# Controller_Board.net
KiCad netlist of a schematic drawn in Altium Designer
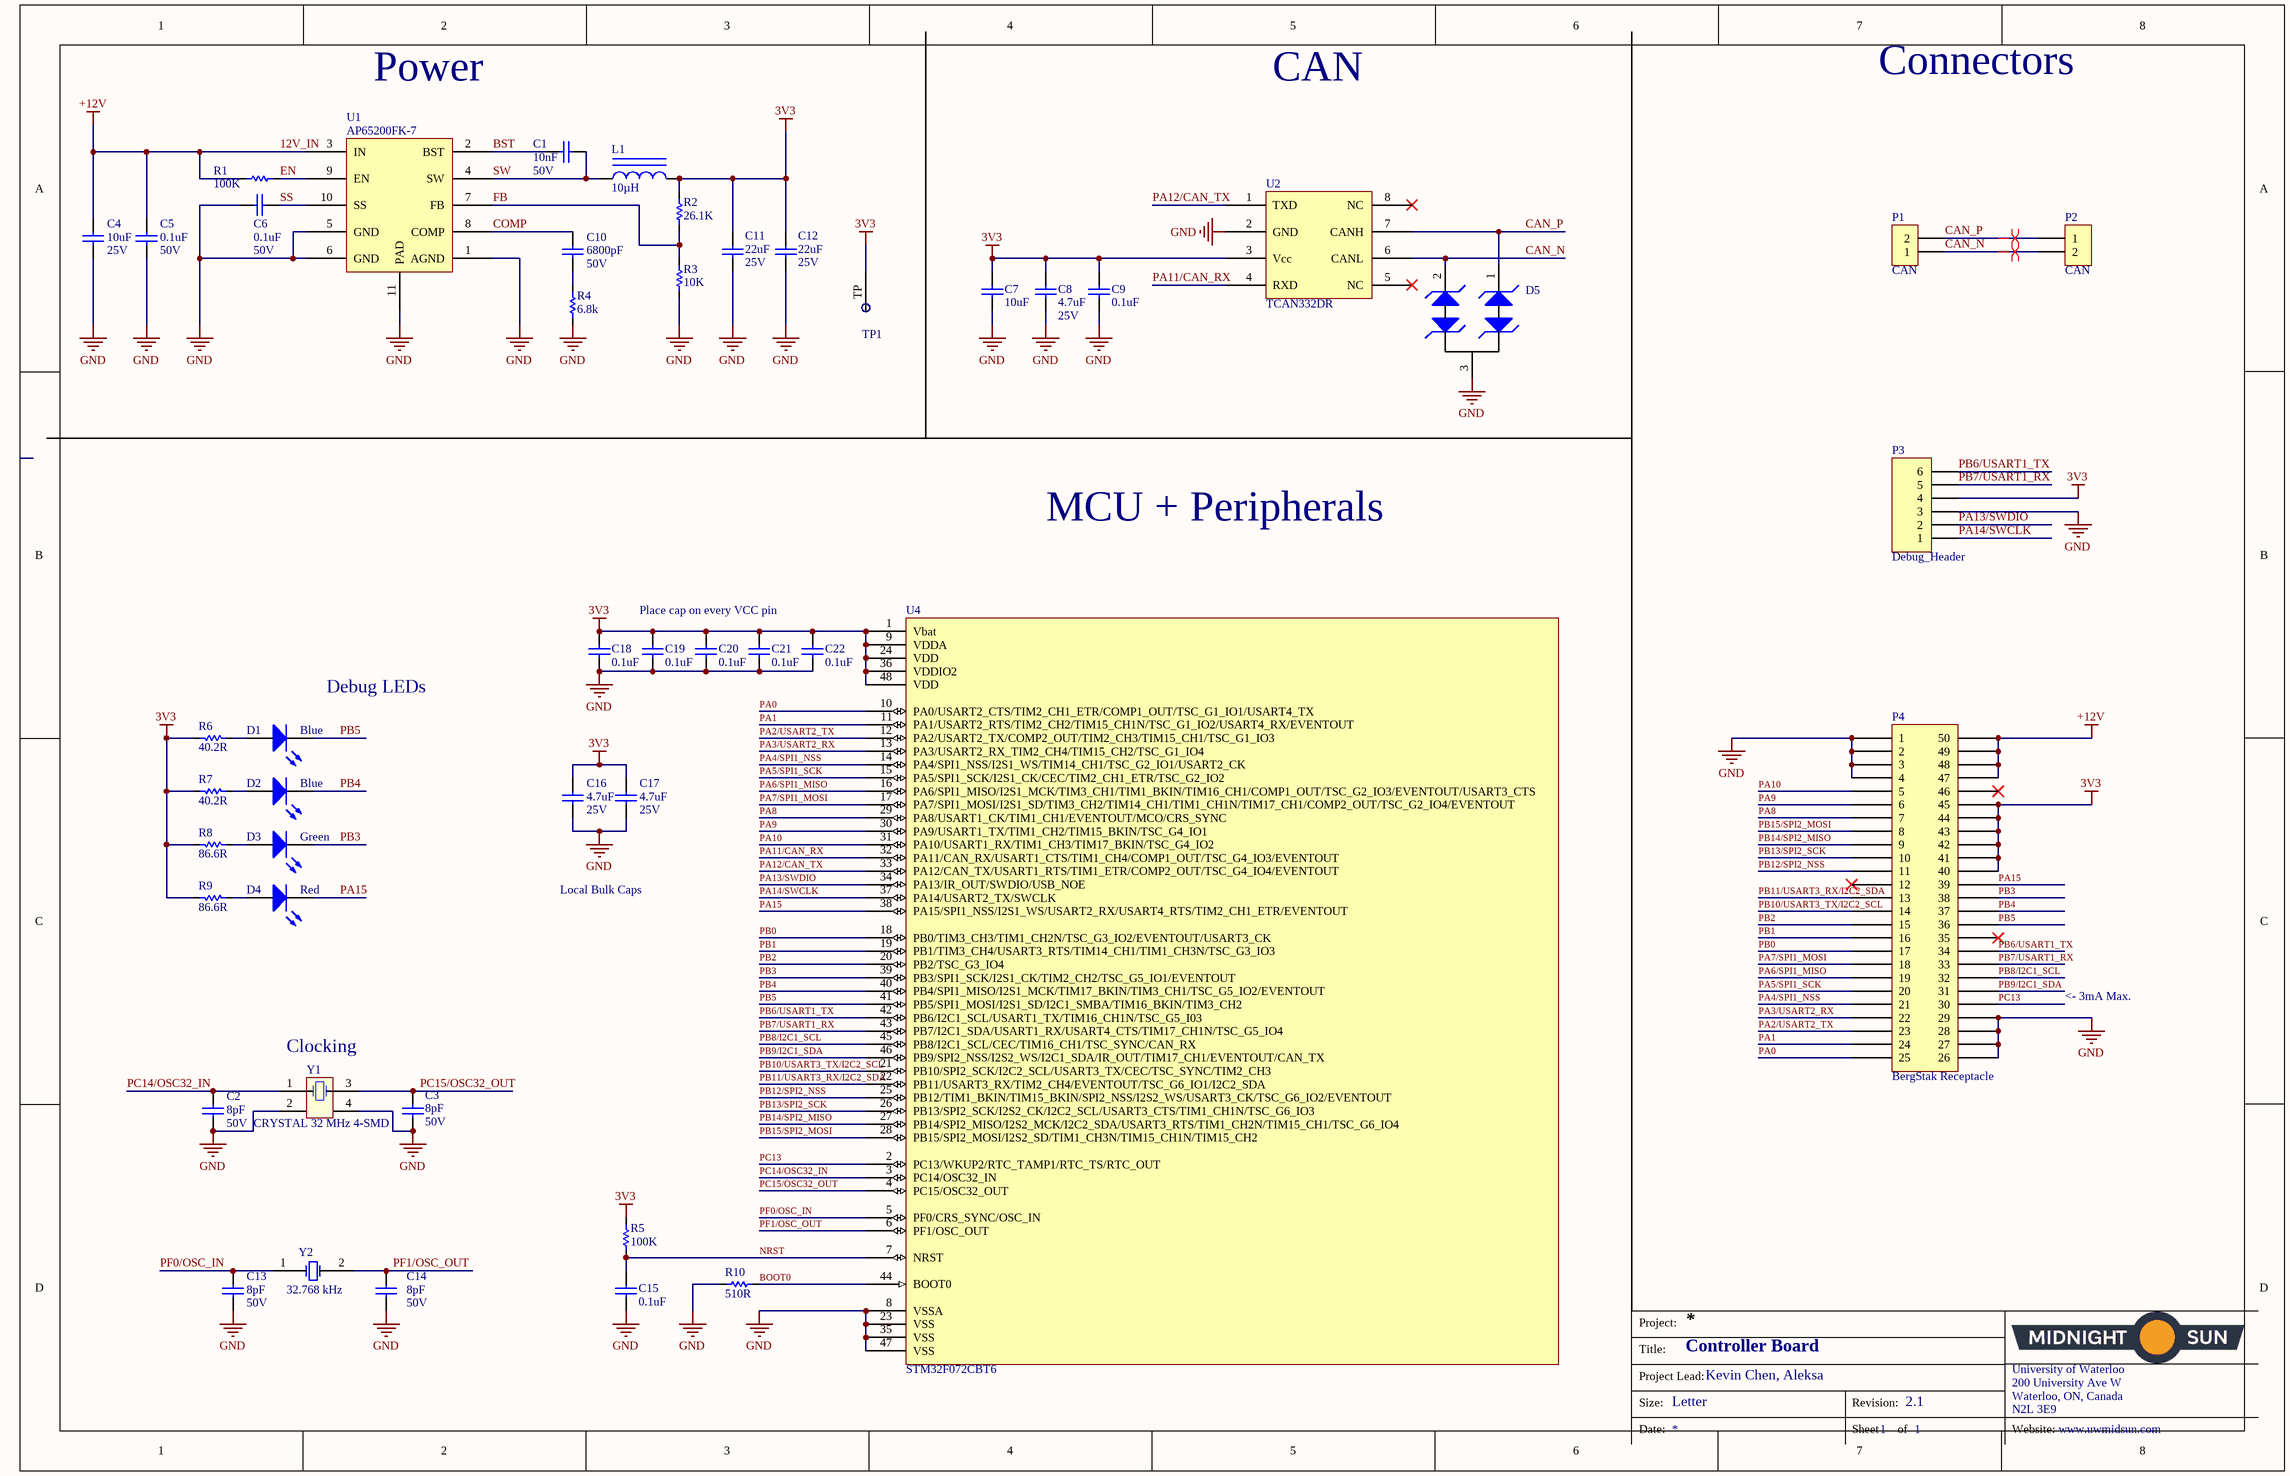
[diagram p0: Controller_Board.SchDoc]

(export (version "E")
  (design (tool "Eeschema 10.0.6"))
  (components
    (comp (ref "C1")
      (value "10nF")
      (footprint "CAPC1608X06N")
      (description "10000pF ±5% 50V Ceramic Capacitor U2J 0603 (1608 Metric)")
      (fields
        (field (name "MANUFACTURER") "Kemet")
        (field (name "MANUFACTURERPARTNUMBER") "C0603C103J5JAC7867")
        (field (name "VOLTAGE") "50V")
      )
      (libsource (lib "Midnight Sun Integrated Library") (part "CAP CER 10nF 50V 5% X7R 0603"))
    )
    (comp (ref "C2")
      (value "8pF")
      (footprint "CAPC1608X06N")
      (description "8pF ±0.5pF 50V Ceramic Capacitor C0G, NP0 0603 (1608 Metric)")
      (fields
        (field (name "MANUFACTURER") "Murata Electronics North America")
        (field (name "MANUFACTURERPARTNUMBER") "GRM1885C1H8R0DA01D")
        (field (name "VOLTAGE") "50V")
      )
      (libsource (lib "Midnight Sun Integrated Library") (part "CAP CER 8PF 50V NP0 0603"))
    )
    (comp (ref "C3")
      (value "8pF")
      (footprint "CAPC1608X06N")
      (description "8pF ±0.5pF 50V Ceramic Capacitor C0G, NP0 0603 (1608 Metric)")
      (fields
        (field (name "MANUFACTURER") "Murata Electronics North America")
        (field (name "MANUFACTURERPARTNUMBER") "GRM1885C1H8R0DA01D")
        (field (name "VOLTAGE") "50V")
      )
      (libsource (lib "Midnight Sun Integrated Library") (part "CAP CER 8PF 50V NP0 0603"))
    )
    (comp (ref "C4")
      (value "10uF")
      (footprint "CAPC1608X06N")
      (description "10µF ±20% 25V Ceramic Capacitor X5R 0603 (1608 Metric)")
      (fields
        (field (name "MANUFACTURER") "Murata Electronics North America")
        (field (name "MANUFACTURERPARTNUMBER") "GRM188R61E106MA73D")
        (field (name "VOLTAGE") "25V")
      )
      (libsource (lib "Midnight Sun Integrated Library") (part "CAP CER 10uF 25V 20% X5R 0603"))
    )
    (comp (ref "C5")
      (value "0.1uF")
      (footprint "CAPC1608X06N")
      (description "0.10µF ±10% 50V Ceramic Capacitor X7R 0603 (1608 Metric)")
      (fields
        (field (name "MANUFACTURER") "AVX Corporation")
        (field (name "MANUFACTURERPARTNUMBER") "06035C104KAT2A")
        (field (name "VOLTAGE") "50V")
      )
      (libsource (lib "Midnight Sun Integrated Library") (part "CAP CER 0.1UF 50V 10% X7R 0603"))
    )
    (comp (ref "C6")
      (value "0.1uF")
      (footprint "CAPC1608X06N")
      (description "0.10µF ±10% 50V Ceramic Capacitor X7R 0603 (1608 Metric)")
      (fields
        (field (name "MANUFACTURER") "AVX Corporation")
        (field (name "MANUFACTURERPARTNUMBER") "06035C104KAT2A")
        (field (name "VOLTAGE") "50V")
      )
      (libsource (lib "Midnight Sun Integrated Library") (part "CAP CER 0.1UF 50V 10% X7R 0603"))
    )
    (comp (ref "C7")
      (value "10uF")
      (footprint "CAPC1608X06N")
      (description "10µF ±20% 25V Ceramic Capacitor X5R 0603 (1608 Metric)")
      (fields
        (field (name "MANUFACTURER") "Murata Electronics North America")
        (field (name "MANUFACTURERPARTNUMBER") "GRM188R61E106MA73D")
      )
      (libsource (lib "Midnight Sun Integrated Library") (part "CAP CER 10uF 25V 20% X5R 0603"))
    )
    (comp (ref "C8")
      (value "4.7uF")
      (footprint "CAPC1608X06N")
      (description "4.7µF ±10% 25V Ceramic Capacitor X5R 0603 (1608 Metric)")
      (fields
        (field (name "MANUFACTURER") "Murata Electronics North America")
        (field (name "MANUFACTURERPARTNUMBER") "GRM188R61E475KE11D")
        (field (name "VOLTAGE") "25V")
      )
      (libsource (lib "Midnight Sun Integrated Library") (part "CAP CER 4.7UF 25V 10% X5R 0603"))
    )
    (comp (ref "C9")
      (value "0.1uF")
      (footprint "CAPC1608X06N")
      (description "0.10µF ±10% 50V Ceramic Capacitor X7R 0603 (1608 Metric)")
      (fields
        (field (name "MANUFACTURER") "AVX Corporation")
        (field (name "MANUFACTURERPARTNUMBER") "06035C104KAT2A")
      )
      (libsource (lib "Midnight Sun Integrated Library") (part "CAP CER 0.1UF 50V 10% X7R 0603"))
    )
    (comp (ref "C10")
      (value "6800pF")
      (footprint "CAPC1608X06N")
      (description "6800pF ±10% 50V Ceramic Capacitor X7R 0603 (1608 Metric)")
      (fields
        (field (name "MANUFACTURER") "Samsung Electro-Mechanics America, Inc.")
        (field (name "MANUFACTURERPARTNUMBER") "CL10B682KB8SFNC")
        (field (name "VOLTAGE") "50V")
      )
      (libsource (lib "Midnight Sun Integrated Library") (part "CAP CER 6800pF 50V 10% X7R 0603"))
    )
    (comp (ref "C11")
      (value "22uF")
      (footprint "CAPC1608X06N")
      (description "0.22µF ±20% 25V Ceramic Capacitor X5R 0603 (1608 Metric)")
      (fields
        (field (name "MANUFACTURER") "Wurth Electronics Inc")
        (field (name "MANUFACTURERPARTNUMBER") "885012106019")
        (field (name "VOLTAGE") "25V")
      )
      (libsource (lib "Midnight Sun Integrated Library") (part "CAP CER 22uF 25V 20% X5R 0603"))
    )
    (comp (ref "C12")
      (value "22uF")
      (footprint "CAPC1608X06N")
      (description "0.22µF ±20% 25V Ceramic Capacitor X5R 0603 (1608 Metric)")
      (fields
        (field (name "MANUFACTURER") "Wurth Electronics Inc")
        (field (name "MANUFACTURERPARTNUMBER") "885012106019")
        (field (name "VOLTAGE") "25V")
      )
      (libsource (lib "Midnight Sun Integrated Library") (part "CAP CER 22uF 25V 20% X5R 0603"))
    )
    (comp (ref "C13")
      (value "8pF")
      (footprint "CAPC1608X06N")
      (description "8pF ±0.5pF 50V Ceramic Capacitor C0G, NP0 0603 (1608 Metric)")
      (fields
        (field (name "MANUFACTURER") "Murata Electronics North America")
        (field (name "MANUFACTURERPARTNUMBER") "GRM1885C1H8R0DA01D")
        (field (name "VOLTAGE") "50V")
      )
      (libsource (lib "Midnight Sun Integrated Library") (part "CAP CER 8PF 50V NP0 0603"))
    )
    (comp (ref "C14")
      (value "8pF")
      (footprint "CAPC1608X06N")
      (description "8pF ±0.5pF 50V Ceramic Capacitor C0G, NP0 0603 (1608 Metric)")
      (fields
        (field (name "MANUFACTURER") "Murata Electronics North America")
        (field (name "MANUFACTURERPARTNUMBER") "GRM1885C1H8R0DA01D")
        (field (name "VOLTAGE") "50V")
      )
      (libsource (lib "Midnight Sun Integrated Library") (part "CAP CER 8PF 50V NP0 0603"))
    )
    (comp (ref "C15")
      (value "0.1uF")
      (footprint "CAPC1608X06N")
      (description "0.10µF ±10% 50V Ceramic Capacitor X7R 0603 (1608 Metric)")
      (fields
        (field (name "MANUFACTURER") "AVX Corporation")
        (field (name "MANUFACTURERPARTNUMBER") "06035C104KAT2A")
      )
      (libsource (lib "Midnight Sun Integrated Library") (part "CAP CER 0.1UF 50V 10% X7R 0603"))
    )
    (comp (ref "C16")
      (value "4.7uF")
      (footprint "CAPC1608X06N")
      (description "4.7µF ±10% 25V Ceramic Capacitor X5R 0603 (1608 Metric)")
      (fields
        (field (name "MANUFACTURER") "Murata Electronics North America")
        (field (name "MANUFACTURERPARTNUMBER") "GRM188R61E475KE11D")
        (field (name "VOLTAGE") "25V")
      )
      (libsource (lib "Midnight Sun Integrated Library") (part "CAP CER 4.7UF 25V 10% X5R 0603"))
    )
    (comp (ref "C17")
      (value "4.7uF")
      (footprint "CAPC1608X06N")
      (description "4.7µF ±10% 25V Ceramic Capacitor X5R 0603 (1608 Metric)")
      (fields
        (field (name "MANUFACTURER") "Murata Electronics North America")
        (field (name "MANUFACTURERPARTNUMBER") "GRM188R61E475KE11D")
        (field (name "VOLTAGE") "25V")
      )
      (libsource (lib "Midnight Sun Integrated Library") (part "CAP CER 4.7UF 25V 10% X5R 0603"))
    )
    (comp (ref "C18")
      (value "0.1uF")
      (footprint "CAPC1608X06N")
      (description "0.10µF ±10% 50V Ceramic Capacitor X7R 0603 (1608 Metric)")
      (fields
        (field (name "MANUFACTURER") "AVX Corporation")
        (field (name "MANUFACTURERPARTNUMBER") "06035C104KAT2A")
      )
      (libsource (lib "Midnight Sun Integrated Library") (part "CAP CER 0.1UF 50V 10% X7R 0603"))
    )
    (comp (ref "C19")
      (value "0.1uF")
      (footprint "CAPC1608X06N")
      (description "0.10µF ±10% 50V Ceramic Capacitor X7R 0603 (1608 Metric)")
      (fields
        (field (name "MANUFACTURER") "AVX Corporation")
        (field (name "MANUFACTURERPARTNUMBER") "06035C104KAT2A")
      )
      (libsource (lib "Midnight Sun Integrated Library") (part "CAP CER 0.1UF 50V 10% X7R 0603"))
    )
    (comp (ref "C20")
      (value "0.1uF")
      (footprint "CAPC1608X06N")
      (description "0.10µF ±10% 50V Ceramic Capacitor X7R 0603 (1608 Metric)")
      (fields
        (field (name "MANUFACTURER") "AVX Corporation")
        (field (name "MANUFACTURERPARTNUMBER") "06035C104KAT2A")
      )
      (libsource (lib "Midnight Sun Integrated Library") (part "CAP CER 0.1UF 50V 10% X7R 0603"))
    )
    (comp (ref "C21")
      (value "0.1uF")
      (footprint "CAPC1608X06N")
      (description "0.10µF ±10% 50V Ceramic Capacitor X7R 0603 (1608 Metric)")
      (fields
        (field (name "MANUFACTURER") "AVX Corporation")
        (field (name "MANUFACTURERPARTNUMBER") "06035C104KAT2A")
      )
      (libsource (lib "Midnight Sun Integrated Library") (part "CAP CER 0.1UF 50V 10% X7R 0603"))
    )
    (comp (ref "C22")
      (value "0.1uF")
      (footprint "CAPC1608X06N")
      (description "0.10µF ±10% 50V Ceramic Capacitor X7R 0603 (1608 Metric)")
      (fields
        (field (name "MANUFACTURER") "AVX Corporation")
        (field (name "MANUFACTURERPARTNUMBER") "06035C104KAT2A")
      )
      (libsource (lib "Midnight Sun Integrated Library") (part "CAP CER 0.1UF 50V 10% X7R 0603"))
    )
    (comp (ref "D1")
      (value "Blue")
      (footprint "DIOC1608X06N")
      (description "LED BLUE CLEAR 0603 SMD")
      (fields
        (field (name "DIGIKEY PART NUMBER") "160-1827-1-ND")
        (field (name "MANUFACTURER") "Lite-On Inc.")
      )
      (libsource (lib "Midnight Sun Integrated Library") (part "LED_BLUE"))
    )
    (comp (ref "D2")
      (value "Blue")
      (footprint "DIOC1608X06N")
      (description "LED BLUE CLEAR 0603 SMD")
      (fields
        (field (name "DIGIKEY PART NUMBER") "160-1827-1-ND")
        (field (name "MANUFACTURER") "Lite-On Inc.")
      )
      (libsource (lib "Midnight Sun Integrated Library") (part "LED_BLUE"))
    )
    (comp (ref "D3")
      (value "Green")
      (footprint "DIOC1608X06N")
      (description "LED GREEN CLEAR 0603 SMD")
      (fields
        (field (name "MANUFACTURER") "Lite-On Inc.")
        (field (name "MANUFACTURER PART NUMBER") "LTST-C193KGKT-5A")
      )
      (libsource (lib "Midnight Sun Integrated Library") (part "LED_GREEN"))
    )
    (comp (ref "D4")
      (value "Red")
      (footprint "DIOC1608X06N")
      (description "Red LED 0603")
      (fields (field (name "MANUFACTURE PART NUMBER") "LTST-C191KRKT"))
      (libsource (lib "Midnight Sun Integrated Library") (part "LED_RED"))
    )
    (comp (ref "D5")
      (value "TVS Diode")
      (footprint "SOT23")
      (description "TVS DIODE 24VWM 70VC SOT23")
      (libsource (lib "Midnight Sun Integrated Library") (part "TVS Diode"))
    )
    (comp (ref "L1")
      (value "10µH")
      (footprint "1210")
      (description "10µH Shielded Wirewound Inductor 900mA 420 mOhm Max 1210 (3225 Metric)")
      (fields
        (field (name "MANUFACTURER") "Murata Electronics North America")
        (field (name "MANUFACTURER PART NUMBER") "1277AS-H-100M=P2")
      )
      (libsource (lib "Midnight Sun Integrated Library") (part "IND 10UH POWDERED IRON 0.9A"))
    )
    (comp (ref "P1")
      (value "CAN")
      (footprint "Dura-Clik, 2POS, 2MM, SMD, Right Angle")
      (description "2 Positions Header, Shrouded Connector 0.079\" (2.00mm) Surface Mount, Right Angle Tin")
      (fields (field (name "MANUFACTURER") "Molex") (field (name "MANUFACTURER PART NUMBER") "5023520200"))
      (libsource (lib "") (part "2 Position DuraClik CAN Connector_1"))
    )
    (comp (ref "P2")
      (value "CAN")
      (footprint "Dura-Clik, 2POS, 2MM, SMD, Right Angle")
      (description "2 Positions Header, Shrouded Connector 0.079\" (2.00mm) Surface Mount, Right Angle Tin")
      (fields (field (name "MANUFACTURER") "Molex") (field (name "MANUFACTURER PART NUMBER") "5023520200"))
      (libsource (lib "Midnight Sun Integrated Library") (part "2 Position DuraClik CAN Connector"))
    )
    (comp (ref "P3")
      (value "Debug_Header")
      (footprint "CONN HEADER 6POS .100\" VERT TIN")
      (description "6 Positions Header, Unshrouded, Breakaway Connector 0.100\" (2.54mm) Surface Mount Tin")
      (fields
        (field (name "MANUFACTURER") "Molex, LLC")
        (field (name "MANUFACTURER PART NUMBER") "0015912060")
      )
      (libsource (lib "Midnight Sun Integrated Library") (part "CONN HEADER 6POS .100 STR TIN"))
    )
    (comp (ref "P4")
      (value "BergStak Receptacle")
      (footprint "609-5227-1-ND")
      (description "50 Position Connector Receptacle, Center Strip Contacts Surface Mount Gold")
      (fields
        (field (name "DIGIKEY PART NUMBER") "609-5227-1-ND")
        (field (name "MANUFACTURER PART NUMBER") "10132798-052100LF")
      )
      (libsource (lib "Midnight Sun Integrated Library") (part "BergStak 50 Position Connector Receptacle"))
    )
    (comp (ref "R1")
      (value "100K")
      (footprint "RESC1608X06N")
      (description "RES SMD 100K OHM 5% 1/10W 0603")
      (fields
        (field (name "MANUFACTURERPARTNUMBER") "RC0603JR-07100KL")
        (field (name "MANUFACTURER") "Yageo")
      )
      (libsource (lib "Midnight Sun Integrated Library") (part "RES 100K OHM 1/8W 5% 0603 SMD"))
    )
    (comp (ref "R2")
      (value "26.1K")
      (footprint "RESC1608X06N")
      (description "RES SMD 26.1K OHM 1% 1/10W 0603")
      (fields
        (field (name "MANUFACTURERPARTNUMBER") "RC0603FR-0726K1L")
        (field (name "MANUFACTURER") "Yageo")
      )
      (libsource (lib "Midnight Sun Integrated Library") (part "RES 26.1K OHM 1/10W 1% 0603 SMD"))
    )
    (comp (ref "R3")
      (value "10K")
      (footprint "RESC1608X06N")
      (description "RES SMD 10K OHM 1% 1/10W 0603")
      (fields (field (name "MANUFACTURE PART NUMBER") "RC0603FR-0710KL") (field (name "TOLERANCE") "1%"))
      (libsource (lib "Midnight Sun Integrated Library") (part "RES SMD 10K OHM 1% 1/10W 0603"))
    )
    (comp (ref "R4")
      (value "6.8k")
      (footprint "RESC1608X06N")
      (description "RES SMD 6.8K OHM 1% 1/10W 0603")
      (fields
        (field (name "MANUFACTURERPARTNUMBER") "RMCF0603FT6K80")
        (field (name "MANUFACTURER") "Stackpole Electronics Inc.")
      )
      (libsource (lib "Midnight Sun Integrated Library") (part "RES 6.8k OHM 1% 1/10W 0603 SMD"))
    )
    (comp (ref "R5")
      (value "100K")
      (footprint "RESC1608X06N")
      (description "RES SMD 100K OHM 5% 1/10W 0603")
      (fields
        (field (name "MANUFACTURERPARTNUMBER") "RC0603JR-07100KL")
        (field (name "MANUFACTURER") "Yageo")
      )
      (libsource (lib "Midnight Sun Integrated Library") (part "RES 100K OHM 1/8W 5% 0603 SMD"))
    )
    (comp (ref "R6")
      (value "40.2R")
      (footprint "RESC1608X06N")
      (description "RES SMD 40.2 OHM 0.5% 1/10W 0603")
      (fields
        (field (name "MANUFACTURERPARTNUMBER") "RT0603DRE0740R2L")
        (field (name "MANUFACTURER") "Yageo")
      )
      (libsource (lib "Midnight Sun Integrated Library") (part "RES 40.2 OHM 0.5% 1/10W 0603 SMD"))
    )
    (comp (ref "R7")
      (value "40.2R")
      (footprint "RESC1608X06N")
      (description "RES SMD 40.2 OHM 0.5% 1/10W 0603")
      (fields
        (field (name "MANUFACTURERPARTNUMBER") "RT0603DRE0740R2L")
        (field (name "MANUFACTURER") "Yageo")
      )
      (libsource (lib "Midnight Sun Integrated Library") (part "RES 40.2 OHM 0.5% 1/10W 0603 SMD"))
    )
    (comp (ref "R8")
      (value "86.6R")
      (footprint "RESC1608X06N")
      (description "RES SMD 86.6 OHM 1% 1/10W 0603")
      (fields
        (field (name "MANUFACTURERPARTNUMBER") "RC0603FR-0786R6L")
        (field (name "MANUFACTURER") "Yageo")
      )
      (libsource (lib "Midnight Sun Integrated Library") (part "RES 86.6 OHM 1% 1/10W 0603 SMD"))
    )
    (comp (ref "R9")
      (value "86.6R")
      (footprint "RESC1608X06N")
      (description "RES SMD 86.6 OHM 1% 1/10W 0603")
      (fields
        (field (name "MANUFACTURERPARTNUMBER") "RC0603FR-0786R6L")
        (field (name "MANUFACTURER") "Yageo")
      )
      (libsource (lib "Midnight Sun Integrated Library") (part "RES 86.6 OHM 1% 1/10W 0603 SMD"))
    )
    (comp (ref "R10")
      (value "510R")
      (footprint "RESC1608X06N")
      (description "RES SMD 510 OHM 5% 1/10W 0603")
      (fields
        (field (name "MANUFACTURERPARTNUMBER") "RC0603JR-07510RL")
        (field (name "MANUFACTURER") "Yageo")
      )
      (libsource (lib "Midnight Sun Integrated Library") (part "RES 510 OHM 1/10W 0603 SMD"))
    )
    (comp (ref "TP1")
      (value "Test Point")
      (footprint "Test Point")
      (libsource (lib "Midnight Sun Integrated Library") (part "Test Point"))
    )
    (comp (ref "U1")
      (value "AP65200FK-7 Buck Switching Regulator")
      (footprint "10-UFDFN")
      (description "Buck Switching Reg IC Positive Adjustable 0.925V 1 Output 2A 10-UFDFN Exposed Pad")
      (fields
        (field (name "DIGIKEY PART NUMBER") "AP65200FK-7DICT-ND")
        (field (name "MANUFACTURER PART NUMBER") "AP65200FK-7")
      )
      (libsource (lib "Midnight Sun Integrated Library") (part "AP65200FK-7 Buck Switching Regulator"))
    )
    (comp (ref "U2")
      (value "TCAN332DR CAN Transceiver")
      (footprint "SOIC8")
      (description "1/1 Transceiver CAN 8-SOIC")
      (fields
        (field (name "DIGIKEY PART NUMBER") "296-43711-1-ND")
        (field (name "MANUFACTURER PART NUMBER") "TCAN332DR")
      )
      (libsource (lib "Midnight Sun Integrated Library") (part "TCAN332DR CAN Transceiver"))
    )
    (comp (ref "U4")
      (value "STM32F072CBT6")
      (footprint "QFN50P700X700X60_HS-49N")
      (fields (field (name "DIGIKEY PART NUMBER") "497-14645-ND"))
      (libsource (lib "Midnight Sun Integrated Library") (part "STM32F072CBT6"))
    )
    (comp (ref "Y1")
      (value "CRYSTAL 32 MHz 4-SMD")
      (footprint "CX2520DB CRYSTAL")
      (description "32MHz ±15ppm Crystal 8pF 50 Ohm -40°C ~ 85°C AEC-Q200 Surface Mount 4-SMD, No Lead")
      (libsource (lib "Midnight Sun Integrated Library") (part "CRYSTAL 32 MHz 4-SMD"))
    )
    (comp (ref "Y2")
      (value "32.768 kHz")
      (footprint "ABS07AIG CRYSTAL")
      (description "32.768kHz ±20ppm Crystal 6pF 50 kOhm -40°C ~ 85°C Surface Mount 4-SOJ, 5.50mm pitch")
      (fields (field (name "MANUFACTURER PART NUMBER") "ABS07AIG-32.768KHZ-9-1-T"))
      (libsource (lib "Midnight Sun Integrated Library") (part "CRYSTAL 32.768KHZ 9PF 2-SMD"))
    )
  )
  (nets
    (net (code "1") (name "+12V") (class "Default")
      (node (ref "C4") (pin "2") (pinfunction "2_2") (pintype "passive"))
      (node (ref "C5") (pin "2") (pinfunction "2_2") (pintype "passive"))
      (node (ref "P4") (pin "47") (pinfunction "47_47") (pintype "passive"))
      (node (ref "P4") (pin "48") (pinfunction "48_48") (pintype "passive"))
      (node (ref "P4") (pin "49") (pinfunction "49_49") (pintype "passive"))
      (node (ref "P4") (pin "50") (pinfunction "50_50") (pintype "passive"))
      (node (ref "R1") (pin "1") (pinfunction "1_1") (pintype "passive"))
      (node (ref "U1") (pin "3") (pinfunction "IN_3") (pintype "passive"))
    )
    (net (code "2") (name "/BOOT0") (class "Default")
      (node (ref "R10") (pin "2") (pinfunction "2_2") (pintype "passive"))
      (node (ref "U4") (pin "44") (pinfunction "BOOT0_44") (pintype "input"))
    )
    (net (code "3") (name "/BST") (class "Default")
      (node (ref "C1") (pin "1") (pinfunction "1_1") (pintype "passive"))
      (node (ref "U1") (pin "2") (pinfunction "BST_2") (pintype "passive"))
    )
    (net (code "4") (name "/CAN_N") (class "Default")
      (node (ref "D5") (pin "2") (pinfunction "Cathode2_2") (pintype "passive"))
      (node (ref "P1") (pin "1") (pinfunction "1_1") (pintype "passive"))
      (node (ref "P2") (pin "2") (pinfunction "2_2") (pintype "passive"))
      (node (ref "U2") (pin "6") (pinfunction "CANL_6") (pintype "passive"))
    )
    (net (code "5") (name "/CAN_P") (class "Default")
      (node (ref "D5") (pin "1") (pinfunction "Cathode1_1") (pintype "passive"))
      (node (ref "P1") (pin "2") (pinfunction "2_2") (pintype "passive"))
      (node (ref "P2") (pin "1") (pinfunction "1_1") (pintype "passive"))
      (node (ref "U2") (pin "7") (pinfunction "CANH_7") (pintype "passive"))
    )
    (net (code "6") (name "/COMP") (class "Default")
      (node (ref "C10") (pin "2") (pinfunction "2_2") (pintype "passive"))
      (node (ref "U1") (pin "8") (pinfunction "COMP_8") (pintype "passive"))
    )
    (net (code "7") (name "/EN") (class "Default")
      (node (ref "R1") (pin "2") (pinfunction "2_2") (pintype "passive"))
      (node (ref "U1") (pin "9") (pinfunction "EN_9") (pintype "passive"))
    )
    (net (code "8") (name "/FB") (class "Default")
      (node (ref "R2") (pin "1") (pinfunction "1_1") (pintype "passive"))
      (node (ref "R3") (pin "2") (pinfunction "2_2") (pintype "passive"))
      (node (ref "U1") (pin "7") (pinfunction "FB_7") (pintype "passive"))
    )
    (net (code "9") (name "/NRST") (class "Default")
      (node (ref "C15") (pin "2") (pinfunction "2_2") (pintype "passive"))
      (node (ref "R5") (pin "1") (pinfunction "1_1") (pintype "passive"))
      (node (ref "U4") (pin "7") (pinfunction "NRST_7") (pintype "bidirectional"))
    )
    (net (code "10") (name "/PA0") (class "Default")
      (node (ref "P4") (pin "25") (pinfunction "25_25") (pintype "passive"))
      (node (ref "U4") (pin "10") (pinfunction "PA0/USART2_CTS/TIM2_CH1_ETR/COMP1_OUT/TSC_G1_IO1/USART4_TX_10") (pintype "bidirectional"))
    )
    (net (code "11") (name "/PA1") (class "Default")
      (node (ref "P4") (pin "24") (pinfunction "24_24") (pintype "passive"))
      (node (ref "U4") (pin "11") (pinfunction "PA1/USART2_RTS/TIM2_CH2/TIM15_CH1N/TSC_G1_IO2/USART4_RX/EVENTOUT_11") (pintype "bidirectional"))
    )
    (net (code "12") (name "/PA2{slash}USART2_TX") (class "Default")
      (node (ref "P4") (pin "23") (pinfunction "23_23") (pintype "passive"))
      (node (ref "U4") (pin "12") (pinfunction "PA2/USART2_TX/COMP2_OUT/TIM2_CH3/TIM15_CH1/TSC_G1_IO3_12") (pintype "bidirectional"))
    )
    (net (code "13") (name "/PA3{slash}USART2_RX") (class "Default")
      (node (ref "P4") (pin "22") (pinfunction "22_22") (pintype "passive"))
      (node (ref "U4") (pin "13") (pinfunction "PA3/USART2_RX_TIM2_CH4/TIM15_CH2/TSC_G1_IO4_13") (pintype "bidirectional"))
    )
    (net (code "14") (name "/PA4{slash}SPI1_NSS") (class "Default")
      (node (ref "P4") (pin "21") (pinfunction "21_21") (pintype "passive"))
      (node (ref "U4") (pin "14") (pinfunction "PA4/SPI1_NSS/I2S1_WS/TIM14_CH1/TSC_G2_IO1/USART2_CK_14") (pintype "bidirectional"))
    )
    (net (code "15") (name "/PA5{slash}SPI1_SCK") (class "Default")
      (node (ref "P4") (pin "20") (pinfunction "20_20") (pintype "passive"))
      (node (ref "U4") (pin "15") (pinfunction "PA5/SPI1_SCK/I2S1_CK/CEC/TIM2_CH1_ETR/TSC_G2_IO2_15") (pintype "bidirectional"))
    )
    (net (code "16") (name "/PA6{slash}SPI1_MISO") (class "Default")
      (node (ref "P4") (pin "19") (pinfunction "19_19") (pintype "passive"))
      (node (ref "U4") (pin "16") (pinfunction "PA6/SPI1_MISO/I2S1_MCK/TIM3_CH1/TIM1_BKIN/TIM16_CH1/COMP1_OUT/TSC_G2_IO3/EVENTOUT/USART3_CTS_16") (pintype "bidirectional"))
    )
    (net (code "17") (name "/PA7{slash}SPI1_MOSI") (class "Default")
      (node (ref "P4") (pin "18") (pinfunction "18_18") (pintype "passive"))
      (node (ref "U4") (pin "17") (pinfunction "PA7/SPI1_MOSI/I2S1_SD/TIM3_CH2/TIM14_CH1/TIM1_CH1N/TIM17_CH1/COMP2_OUT/TSC_G2_IO4/EVENTOUT_17") (pintype "bidirectional"))
    )
    (net (code "18") (name "/PA8") (class "Default")
      (node (ref "P4") (pin "7") (pinfunction "7_7") (pintype "passive"))
      (node (ref "U4") (pin "29") (pinfunction "PA8/USART1_CK/TIM1_CH1/EVENTOUT/MCO/CRS_SYNC_29") (pintype "bidirectional"))
    )
    (net (code "19") (name "/PA9") (class "Default")
      (node (ref "P4") (pin "6") (pinfunction "6_6") (pintype "passive"))
      (node (ref "U4") (pin "30") (pinfunction "PA9/USART1_TX/TIM1_CH2/TIM15_BKIN/TSC_G4_IO1_30") (pintype "bidirectional"))
    )
    (net (code "20") (name "/PA10") (class "Default")
      (node (ref "P4") (pin "5") (pinfunction "5_5") (pintype "passive"))
      (node (ref "U4") (pin "31") (pinfunction "PA10/USART1_RX/TIM1_CH3/TIM17_BKIN/TSC_G4_IO2_31") (pintype "bidirectional"))
    )
    (net (code "21") (name "/PA11{slash}CAN_RX") (class "Default")
      (node (ref "U2") (pin "4") (pinfunction "RXD_4") (pintype "passive"))
      (node (ref "U4") (pin "32") (pinfunction "PA11/CAN_RX/USART1_CTS/TIM1_CH4/COMP1_OUT/TSC_G4_IO3/EVENTOUT_32") (pintype "bidirectional"))
    )
    (net (code "22") (name "/PA12{slash}CAN_TX") (class "Default")
      (node (ref "U2") (pin "1") (pinfunction "TXD_1") (pintype "passive"))
      (node (ref "U4") (pin "33") (pinfunction "PA12/CAN_TX/USART1_RTS/TIM1_ETR/COMP2_OUT/TSC_G4_IO4/EVENTOUT_33") (pintype "bidirectional"))
    )
    (net (code "23") (name "/PA13{slash}SWDIO") (class "Default")
      (node (ref "P3") (pin "2") (pinfunction "2_2") (pintype "passive"))
      (node (ref "U4") (pin "34") (pinfunction "PA13/IR_OUT/SWDIO/USB_NOE_34") (pintype "bidirectional"))
    )
    (net (code "24") (name "/PA14{slash}SWCLK") (class "Default")
      (node (ref "P3") (pin "1") (pinfunction "1_1") (pintype "passive"))
      (node (ref "U4") (pin "37") (pinfunction "PA14/USART2_TX/SWCLK_37") (pintype "bidirectional"))
    )
    (net (code "25") (name "/PA15") (class "Default")
      (node (ref "D4") (pin "2") (pinfunction "K_2") (pintype "passive"))
      (node (ref "P4") (pin "39") (pinfunction "39_39") (pintype "passive"))
      (node (ref "U4") (pin "38") (pinfunction "PA15/SPI1_NSS/I2S1_WS/USART2_RX/USART4_RTS/TIM2_CH1_ETR/EVENTOUT_38") (pintype "bidirectional"))
    )
    (net (code "26") (name "/PB0") (class "Default")
      (node (ref "P4") (pin "17") (pinfunction "17_17") (pintype "passive"))
      (node (ref "U4") (pin "18") (pinfunction "PB0/TIM3_CH3/TIM1_CH2N/TSC_G3_IO2/EVENTOUT/USART3_CK_18") (pintype "bidirectional"))
    )
    (net (code "27") (name "/PB1") (class "Default")
      (node (ref "P4") (pin "16") (pinfunction "16_16") (pintype "passive"))
      (node (ref "U4") (pin "19") (pinfunction "PB1/TIM3_CH4/USART3_RTS/TIM14_CH1/TIM1_CH3N/TSC_G3_IO3_19") (pintype "bidirectional"))
    )
    (net (code "28") (name "/PB2") (class "Default")
      (node (ref "P4") (pin "15") (pinfunction "15_15") (pintype "passive"))
      (node (ref "U4") (pin "20") (pinfunction "PB2/TSC_G3_IO4_20") (pintype "bidirectional"))
    )
    (net (code "29") (name "/PB3") (class "Default")
      (node (ref "D3") (pin "2") (pinfunction "K_2") (pintype "passive"))
      (node (ref "P4") (pin "38") (pinfunction "38_38") (pintype "passive"))
      (node (ref "U4") (pin "39") (pinfunction "PB3/SPI1_SCK/I2S1_CK/TIM2_CH2/TSC_G5_IO1/EVENTOUT_39") (pintype "bidirectional"))
    )
    (net (code "30") (name "/PB4") (class "Default")
      (node (ref "D2") (pin "2") (pinfunction "K_2") (pintype "passive"))
      (node (ref "P4") (pin "37") (pinfunction "37_37") (pintype "passive"))
      (node (ref "U4") (pin "40") (pinfunction "PB4/SPI1_MISO/I2S1_MCK/TIM17_BKIN/TIM3_CH1/TSC_G5_IO2/EVENTOUT_40") (pintype "bidirectional"))
    )
    (net (code "31") (name "/PB5") (class "Default")
      (node (ref "D1") (pin "2") (pinfunction "K_2") (pintype "passive"))
      (node (ref "P4") (pin "36") (pinfunction "36_36") (pintype "passive"))
      (node (ref "U4") (pin "41") (pinfunction "PB5/SPI1_MOSI/I2S1_SD/I2C1_SMBA/TIM16_BKIN/TIM3_CH2_41") (pintype "bidirectional"))
    )
    (net (code "32") (name "/PB6{slash}USART1_TX") (class "Default")
      (node (ref "P3") (pin "6") (pinfunction "6_6") (pintype "passive"))
      (node (ref "P4") (pin "34") (pinfunction "34_34") (pintype "passive"))
      (node (ref "U4") (pin "42") (pinfunction "PB6/I2C1_SCL/USART1_TX/TIM16_CH1N/TSC_G5_I03_42") (pintype "bidirectional"))
    )
    (net (code "33") (name "/PB7{slash}USART1_RX") (class "Default")
      (node (ref "P3") (pin "5") (pinfunction "5_5") (pintype "passive"))
      (node (ref "P4") (pin "33") (pinfunction "33_33") (pintype "passive"))
      (node (ref "U4") (pin "43") (pinfunction "PB7/I2C1_SDA/USART1_RX/USART4_CTS/TIM17_CH1N/TSC_G5_IO4_43") (pintype "bidirectional"))
    )
    (net (code "34") (name "/PB8{slash}I2C1_SCL") (class "Default")
      (node (ref "P4") (pin "32") (pinfunction "32_32") (pintype "passive"))
      (node (ref "U4") (pin "45") (pinfunction "PB8/I2C1_SCL/CEC/TIM16_CH1/TSC_SYNC/CAN_RX_45") (pintype "bidirectional"))
    )
    (net (code "35") (name "/PB9{slash}I2C1_SDA") (class "Default")
      (node (ref "P4") (pin "31") (pinfunction "31_31") (pintype "passive"))
      (node (ref "U4") (pin "46") (pinfunction "PB9/SPI2_NSS/I2S2_WS/I2C1_SDA/IR_OUT/TIM17_CH1/EVENTOUT/CAN_TX_46") (pintype "bidirectional"))
    )
    (net (code "36") (name "/PB10{slash}USART3_TX{slash}I2C2_SCL") (class "Default")
      (node (ref "P4") (pin "14") (pinfunction "14_14") (pintype "passive"))
      (node (ref "U4") (pin "21") (pinfunction "PB10/SPI2_SCK/I2C2_SCL/USART3_TX/CEC/TSC_SYNC/TIM2_CH3_21") (pintype "bidirectional"))
    )
    (net (code "37") (name "/PB11{slash}USART3_RX{slash}I2C2_SDA") (class "Default")
      (node (ref "P4") (pin "13") (pinfunction "13_13") (pintype "passive"))
      (node (ref "U4") (pin "22") (pinfunction "PB11/USART3_RX/TIM2_CH4/EVENTOUT/TSC_G6_IO1/I2C2_SDA_22") (pintype "bidirectional"))
    )
    (net (code "38") (name "/PB12{slash}SPI2_NSS") (class "Default")
      (node (ref "P4") (pin "11") (pinfunction "11_11") (pintype "passive"))
      (node (ref "U4") (pin "25") (pinfunction "PB12/TIM1_BKIN/TIM15_BKIN/SPI2_NSS/I2S2_WS/USART3_CK/TSC_G6_IO2/EVENTOUT_25") (pintype "bidirectional"))
    )
    (net (code "39") (name "/PB13{slash}SPI2_SCK") (class "Default")
      (node (ref "P4") (pin "10") (pinfunction "10_10") (pintype "passive"))
      (node (ref "U4") (pin "26") (pinfunction "PB13/SPI2_SCK/I2S2_CK/I2C2_SCL/USART3_CTS/TIM1_CH1N/TSC_G6_IO3_26") (pintype "bidirectional"))
    )
    (net (code "40") (name "/PB14{slash}SPI2_MISO") (class "Default")
      (node (ref "P4") (pin "9") (pinfunction "9_9") (pintype "passive"))
      (node (ref "U4") (pin "27") (pinfunction "PB14/SPI2_MISO/I2S2_MCK/I2C2_SDA/USART3_RTS/TIM1_CH2N/TIM15_CH1/TSC_G6_IO4_27") (pintype "bidirectional"))
    )
    (net (code "41") (name "/PB15{slash}SPI2_MOSI") (class "Default")
      (node (ref "P4") (pin "8") (pinfunction "8_8") (pintype "passive"))
      (node (ref "U4") (pin "28") (pinfunction "PB15/SPI2_MOSI/I2S2_SD/TIM1_CH3N/TIM15_CH1N/TIM15_CH2_28") (pintype "bidirectional"))
    )
    (net (code "42") (name "/PC13") (class "Default")
      (node (ref "P4") (pin "30") (pinfunction "30_30") (pintype "passive"))
      (node (ref "U4") (pin "2") (pinfunction "PC13/WKUP2/RTC_TAMP1/RTC_TS/RTC_OUT_2") (pintype "bidirectional"))
    )
    (net (code "43") (name "/PC14{slash}OSC32_IN") (class "Default")
      (node (ref "C2") (pin "2") (pinfunction "2_2") (pintype "passive"))
      (node (ref "U4") (pin "3") (pinfunction "PC14/OSC32_IN_3") (pintype "bidirectional"))
      (node (ref "Y1") (pin "1") (pinfunction "OSC1_1") (pintype "passive"))
    )
    (net (code "44") (name "/PC15{slash}OSC32_OUT") (class "Default")
      (node (ref "C3") (pin "2") (pinfunction "2_2") (pintype "passive"))
      (node (ref "U4") (pin "4") (pinfunction "PC15/OSC32_OUT_4") (pintype "bidirectional"))
      (node (ref "Y1") (pin "3") (pinfunction "OSC2_3") (pintype "passive"))
    )
    (net (code "45") (name "/PF0{slash}OSC_IN") (class "Default")
      (node (ref "C13") (pin "2") (pinfunction "2_2") (pintype "passive"))
      (node (ref "U4") (pin "5") (pinfunction "PF0/CRS_SYNC/OSC_IN_5") (pintype "bidirectional"))
      (node (ref "Y2") (pin "1") (pinfunction "1_1") (pintype "passive"))
    )
    (net (code "46") (name "/PF1{slash}OSC_OUT") (class "Default")
      (node (ref "C14") (pin "2") (pinfunction "2_2") (pintype "passive"))
      (node (ref "U4") (pin "6") (pinfunction "PF1/OSC_OUT_6") (pintype "bidirectional"))
      (node (ref "Y2") (pin "2") (pinfunction "2_2") (pintype "passive"))
    )
    (net (code "47") (name "/SS") (class "Default")
      (node (ref "C6") (pin "1") (pinfunction "1_1") (pintype "passive"))
      (node (ref "U1") (pin "10") (pinfunction "SS_10") (pintype "passive"))
    )
    (net (code "48") (name "/SW") (class "Default")
      (node (ref "C1") (pin "2") (pinfunction "2_2") (pintype "passive"))
      (node (ref "L1") (pin "1") (pinfunction "1_1") (pintype "passive"))
      (node (ref "U1") (pin "4") (pinfunction "SW_4") (pintype "passive"))
    )
    (net (code "49") (name "3V3") (class "Default")
      (node (ref "C11") (pin "2") (pinfunction "2_2") (pintype "passive"))
      (node (ref "C12") (pin "2") (pinfunction "2_2") (pintype "passive"))
      (node (ref "C16") (pin "2") (pinfunction "2_2") (pintype "passive"))
      (node (ref "C17") (pin "2") (pinfunction "2_2") (pintype "passive"))
      (node (ref "C18") (pin "2") (pinfunction "2_2") (pintype "passive"))
      (node (ref "C19") (pin "2") (pinfunction "2_2") (pintype "passive"))
      (node (ref "C20") (pin "2") (pinfunction "2_2") (pintype "passive"))
      (node (ref "C21") (pin "2") (pinfunction "2_2") (pintype "passive"))
      (node (ref "C22") (pin "2") (pinfunction "2_2") (pintype "passive"))
      (node (ref "C7") (pin "2") (pinfunction "2_2") (pintype "passive"))
      (node (ref "C8") (pin "2") (pinfunction "2_2") (pintype "passive"))
      (node (ref "C9") (pin "2") (pinfunction "2_2") (pintype "passive"))
      (node (ref "L1") (pin "2") (pinfunction "2_2") (pintype "passive"))
      (node (ref "P3") (pin "4") (pinfunction "4_4") (pintype "passive"))
      (node (ref "P4") (pin "40") (pinfunction "40_40") (pintype "passive"))
      (node (ref "P4") (pin "41") (pinfunction "41_41") (pintype "passive"))
      (node (ref "P4") (pin "42") (pinfunction "42_42") (pintype "passive"))
      (node (ref "P4") (pin "43") (pinfunction "43_43") (pintype "passive"))
      (node (ref "P4") (pin "44") (pinfunction "44_44") (pintype "passive"))
      (node (ref "P4") (pin "45") (pinfunction "45_45") (pintype "passive"))
      (node (ref "R2") (pin "2") (pinfunction "2_2") (pintype "passive"))
      (node (ref "R5") (pin "2") (pinfunction "2_2") (pintype "passive"))
      (node (ref "R6") (pin "2") (pinfunction "2_2") (pintype "passive"))
      (node (ref "R7") (pin "2") (pinfunction "2_2") (pintype "passive"))
      (node (ref "R8") (pin "2") (pinfunction "2_2") (pintype "passive"))
      (node (ref "R9") (pin "2") (pinfunction "2_2") (pintype "passive"))
      (node (ref "TP1") (pin "TP") (pinfunction "1_TP") (pintype "passive"))
      (node (ref "U2") (pin "3") (pinfunction "Vcc_3") (pintype "passive"))
      (node (ref "U4") (pin "1") (pinfunction "Vbat_1") (pintype "power_in"))
      (node (ref "U4") (pin "24") (pinfunction "VDD_24") (pintype "power_in"))
      (node (ref "U4") (pin "36") (pinfunction "VDDIO2_36") (pintype "power_in"))
      (node (ref "U4") (pin "48") (pinfunction "VDD_48") (pintype "power_in"))
      (node (ref "U4") (pin "9") (pinfunction "VDDA_9") (pintype "power_in"))
    )
    (net (code "50") (name "GND") (class "Default")
      (node (ref "C11") (pin "1") (pinfunction "1_1") (pintype "passive"))
      (node (ref "C12") (pin "1") (pinfunction "1_1") (pintype "passive"))
      (node (ref "C13") (pin "1") (pinfunction "1_1") (pintype "passive"))
      (node (ref "C14") (pin "1") (pinfunction "1_1") (pintype "passive"))
      (node (ref "C15") (pin "1") (pinfunction "1_1") (pintype "passive"))
      (node (ref "C16") (pin "1") (pinfunction "1_1") (pintype "passive"))
      (node (ref "C17") (pin "1") (pinfunction "1_1") (pintype "passive"))
      (node (ref "C18") (pin "1") (pinfunction "1_1") (pintype "passive"))
      (node (ref "C19") (pin "1") (pinfunction "1_1") (pintype "passive"))
      (node (ref "C2") (pin "1") (pinfunction "1_1") (pintype "passive"))
      (node (ref "C20") (pin "1") (pinfunction "1_1") (pintype "passive"))
      (node (ref "C21") (pin "1") (pinfunction "1_1") (pintype "passive"))
      (node (ref "C22") (pin "1") (pinfunction "1_1") (pintype "passive"))
      (node (ref "C3") (pin "1") (pinfunction "1_1") (pintype "passive"))
      (node (ref "C4") (pin "1") (pinfunction "1_1") (pintype "passive"))
      (node (ref "C5") (pin "1") (pinfunction "1_1") (pintype "passive"))
      (node (ref "C6") (pin "2") (pinfunction "2_2") (pintype "passive"))
      (node (ref "C7") (pin "1") (pinfunction "1_1") (pintype "passive"))
      (node (ref "C8") (pin "1") (pinfunction "1_1") (pintype "passive"))
      (node (ref "C9") (pin "1") (pinfunction "1_1") (pintype "passive"))
      (node (ref "D5") (pin "3") (pinfunction "Common_Cathode_3") (pintype "power_in"))
      (node (ref "P3") (pin "3") (pinfunction "3_3") (pintype "passive"))
      (node (ref "P4") (pin "1") (pinfunction "1_1") (pintype "passive"))
      (node (ref "P4") (pin "2") (pinfunction "2_2") (pintype "passive"))
      (node (ref "P4") (pin "26") (pinfunction "26_26") (pintype "passive"))
      (node (ref "P4") (pin "27") (pinfunction "27_27") (pintype "passive"))
      (node (ref "P4") (pin "28") (pinfunction "28_28") (pintype "passive"))
      (node (ref "P4") (pin "29") (pinfunction "29_29") (pintype "passive"))
      (node (ref "P4") (pin "3") (pinfunction "3_3") (pintype "passive"))
      (node (ref "P4") (pin "4") (pinfunction "4_4") (pintype "passive"))
      (node (ref "R10") (pin "1") (pinfunction "1_1") (pintype "passive"))
      (node (ref "R3") (pin "1") (pinfunction "1_1") (pintype "passive"))
      (node (ref "R4") (pin "1") (pinfunction "1_1") (pintype "passive"))
      (node (ref "U1") (pin "1") (pinfunction "AGND_1") (pintype "passive"))
      (node (ref "U1") (pin "11") (pinfunction "PAD_11") (pintype "passive"))
      (node (ref "U1") (pin "5") (pinfunction "GND_5") (pintype "power_in"))
      (node (ref "U1") (pin "6") (pinfunction "GND_6") (pintype "power_in"))
      (node (ref "U2") (pin "2") (pinfunction "GND_2") (pintype "passive"))
      (node (ref "U4") (pin "23") (pinfunction "VSS_23") (pintype "power_in"))
      (node (ref "U4") (pin "35") (pinfunction "VSS_35") (pintype "power_in"))
      (node (ref "U4") (pin "47") (pinfunction "VSS_47") (pintype "power_in"))
      (node (ref "U4") (pin "8") (pinfunction "VSSA_8") (pintype "power_in"))
      (node (ref "Y1") (pin "2") (pinfunction "2_2") (pintype "passive"))
      (node (ref "Y1") (pin "4") (pinfunction "3_4") (pintype "passive"))
    )
    (net (code "51") (name "Net-(C10-Pad1)") (class "Default")
      (node (ref "C10") (pin "1") (pinfunction "1_1") (pintype "passive"))
      (node (ref "R4") (pin "2") (pinfunction "2_2") (pintype "passive"))
    )
    (net (code "52") (name "Net-(D1-A)") (class "Default")
      (node (ref "D1") (pin "1") (pinfunction "A_1") (pintype "passive"))
      (node (ref "R6") (pin "1") (pinfunction "1_1") (pintype "passive"))
    )
    (net (code "53") (name "Net-(D2-A)") (class "Default")
      (node (ref "D2") (pin "1") (pinfunction "A_1") (pintype "passive"))
      (node (ref "R7") (pin "1") (pinfunction "1_1") (pintype "passive"))
    )
    (net (code "54") (name "Net-(D3-A)") (class "Default")
      (node (ref "D3") (pin "1") (pinfunction "A_1") (pintype "passive"))
      (node (ref "R8") (pin "1") (pinfunction "1_1") (pintype "passive"))
    )
    (net (code "55") (name "Net-(D4-A)") (class "Default")
      (node (ref "D4") (pin "1") (pinfunction "A_1") (pintype "passive"))
      (node (ref "R9") (pin "1") (pinfunction "1_1") (pintype "passive"))
    )
    (net (code "56") (name "unconnected-(P4-Pad12)") (class "Default")
      (node (ref "P4") (pin "12") (pinfunction "12_12") (pintype "passive+no_connect"))
    )
    (net (code "57") (name "unconnected-(P4-Pad35)") (class "Default")
      (node (ref "P4") (pin "35") (pinfunction "35_35") (pintype "passive+no_connect"))
    )
    (net (code "58") (name "unconnected-(P4-Pad46)") (class "Default")
      (node (ref "P4") (pin "46") (pinfunction "46_46") (pintype "passive+no_connect"))
    )
    (net (code "59") (name "unconnected-(U2-NC-Pad5)") (class "Default")
      (node (ref "U2") (pin "5") (pinfunction "NC_5") (pintype "passive+no_connect"))
    )
    (net (code "60") (name "unconnected-(U2-NC-Pad8)") (class "Default")
      (node (ref "U2") (pin "8") (pinfunction "NC_8") (pintype "passive+no_connect"))
    )
  )
)
